# AST1032.net
KiCad netlist of a schematic drawn in EAGLE
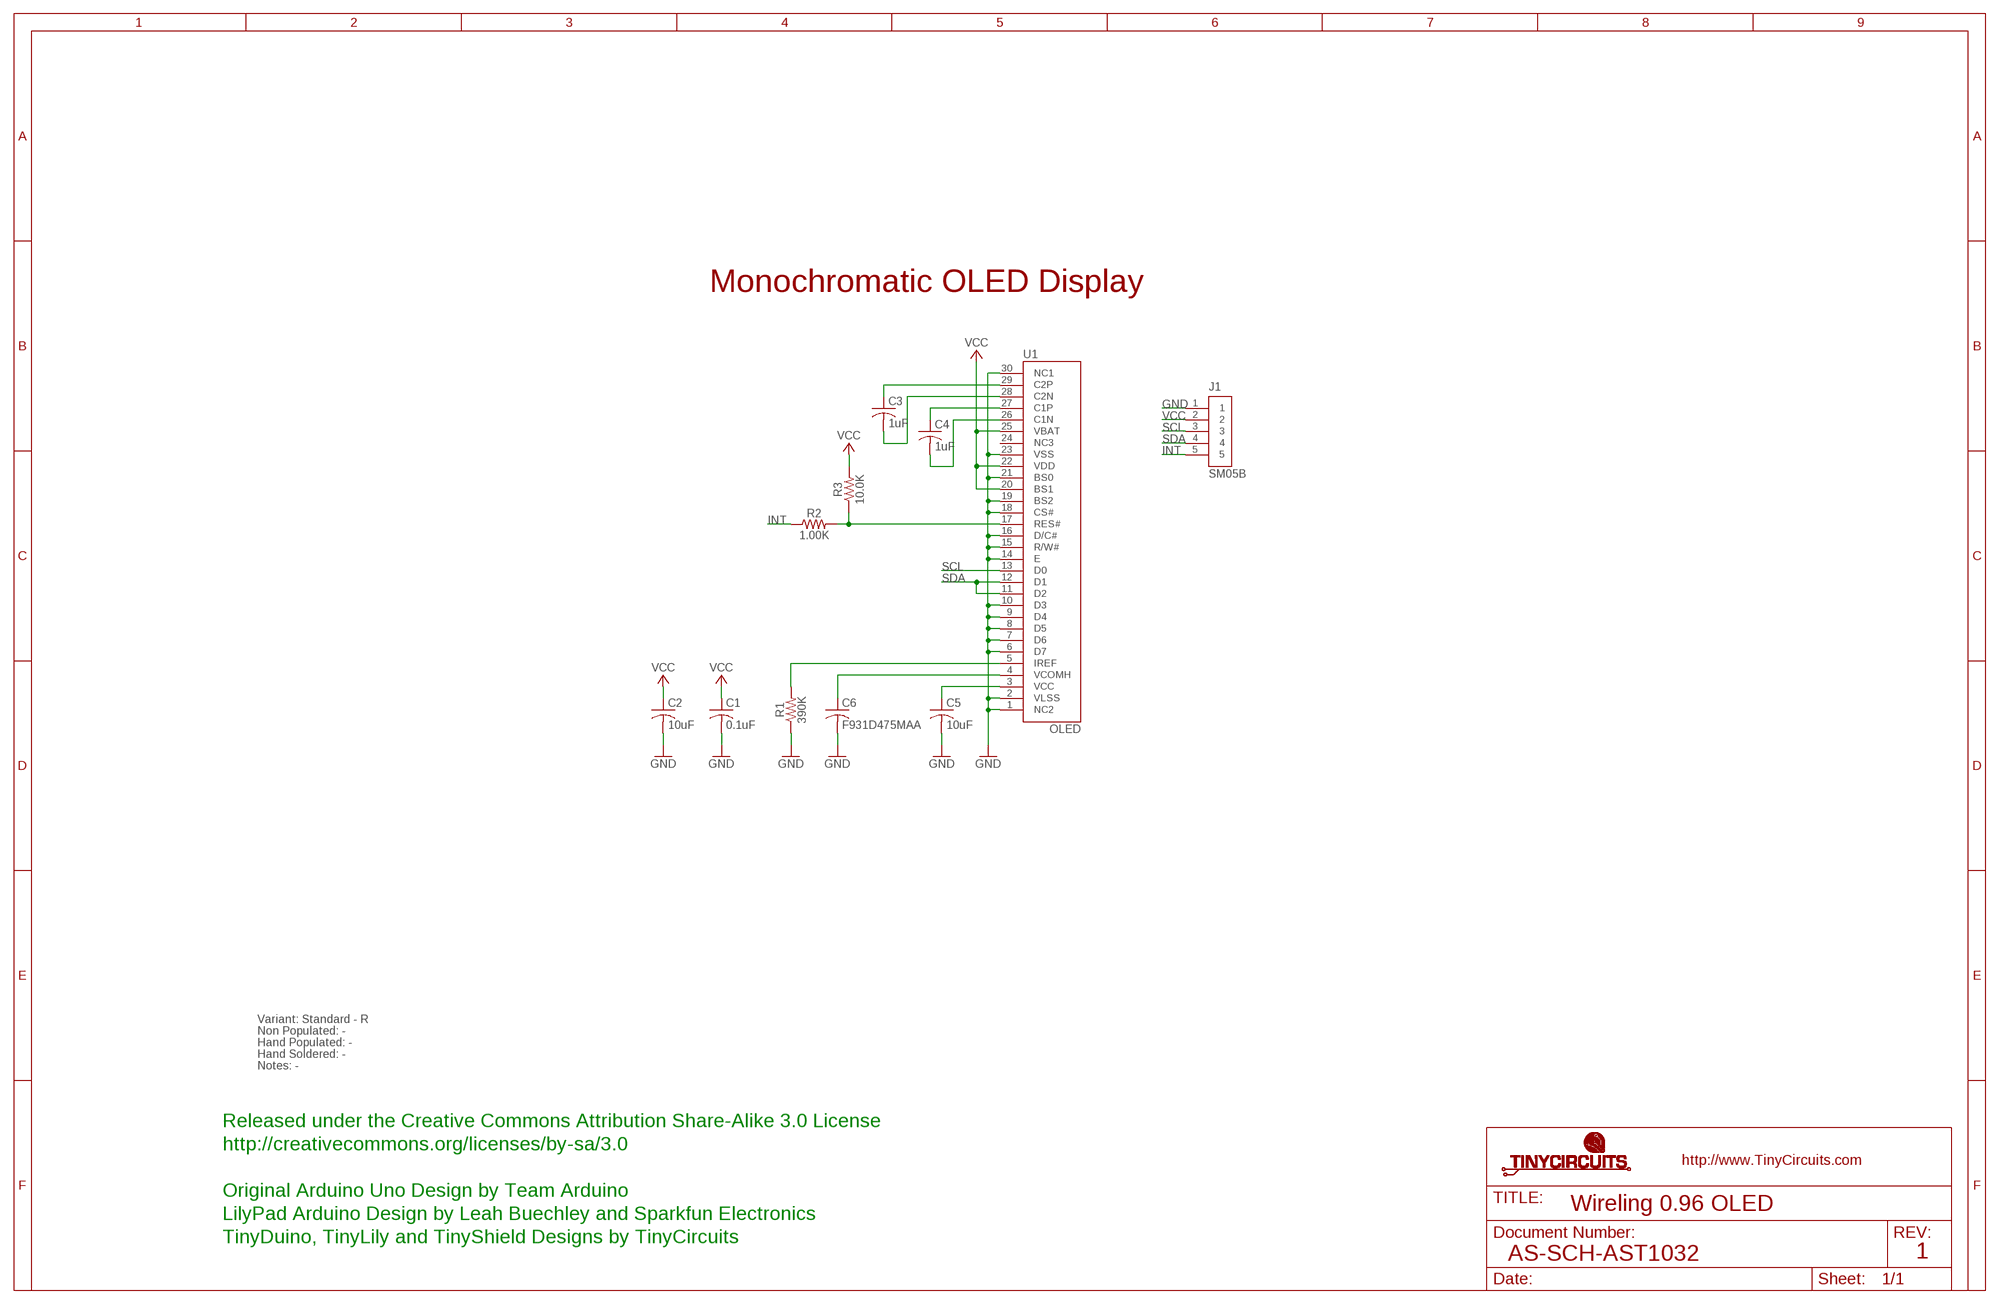
[diagram p0: schematic, sheet 1]

(export (version "E")
  (design (tool "Eeschema 10.0.6"))
  (components
    (comp (ref "C1")
      (value "0.1uF")
      (footprint "eagle-import:C0402")
      (fields (field (name "PARTNO") "AS-ITM-00008"))
      (libsource (lib "eagle-import") (part "AS-ITM-00008"))
    )
    (comp (ref "C2")
      (value "10uF")
      (footprint "eagle-import:C0603")
      (fields (field (name "PARTNO") "AS-ITM-00002"))
      (libsource (lib "eagle-import") (part "AS-ITM-00002"))
    )
    (comp (ref "C3")
      (value "1uF")
      (footprint "eagle-import:C0603")
      (fields (field (name "PARTNO") "AS-ITM-00347"))
      (libsource (lib "eagle-import") (part "AS-ITM-00347"))
    )
    (comp (ref "C4")
      (value "1uF")
      (footprint "eagle-import:C0603")
      (fields (field (name "PARTNO") "AS-ITM-00347"))
      (libsource (lib "eagle-import") (part "AS-ITM-00347"))
    )
    (comp (ref "C5")
      (value "10uF")
      (footprint "eagle-import:C0805")
      (fields (field (name "PARTNO") "AS-ITM-00045"))
      (libsource (lib "eagle-import") (part "AS-ITM-00045"))
    )
    (comp (ref "C6")
      (value "F931D475MAA")
      (footprint "eagle-import:1206_CAP_TANT")
      (fields (field (name "PARTNO") "AS-ITM-00232"))
      (libsource (lib "eagle-import") (part "AS-ITM-00232"))
    )
    (comp (ref "J1")
      (value "SM05B")
      (footprint "eagle-import:JST_SH_5X1")
      (fields (field (name "PARTNO") "AS-ITM-00340"))
      (libsource (lib "eagle-import") (part "AS-ITM-00340"))
    )
    (comp (ref "R1")
      (value "390K")
      (footprint "eagle-import:0402")
      (fields (field (name "PARTNO") "AS-ITM-00346"))
      (libsource (lib "eagle-import") (part "AS-ITM-00346"))
    )
    (comp (ref "R2")
      (value "1.00K")
      (footprint "eagle-import:0402")
      (fields (field (name "PARTNO") "AS-ITM-00003") (field (name "PARTNO_1") "AS-ITM-00003"))
      (libsource (lib "eagle-import") (part "AS-ITM-00003"))
    )
    (comp (ref "R3")
      (value "10.0K")
      (footprint "eagle-import:0402")
      (fields (field (name "PARTNO") "AS-ITM-00032"))
      (libsource (lib "eagle-import") (part "AS-ITM-00032"))
    )
    (comp (ref "U1")
      (value "OLED")
      (footprint "eagle-import:OLED_WHITE_30P")
      (fields (field (name "PARTNO") "AS-ITM-00341"))
      (libsource (lib "eagle-import") (part "AS-ITM-003411"))
    )
  )
  (nets
    (net (code "1") (name "/INT") (class "Default")
      (node (ref "J1") (pin "5") (pinfunction "5_5") (pintype "bidirectional"))
      (node (ref "R2") (pin "1") (pinfunction "1_1") (pintype "passive"))
    )
    (net (code "2") (name "/SCL") (class "Default")
      (node (ref "J1") (pin "3") (pinfunction "3_3") (pintype "bidirectional"))
      (node (ref "U1") (pin "13") (pinfunction "D0_13") (pintype "bidirectional"))
    )
    (net (code "3") (name "/SDA") (class "Default")
      (node (ref "J1") (pin "4") (pinfunction "4_4") (pintype "bidirectional"))
      (node (ref "U1") (pin "11") (pinfunction "D2_11") (pintype "bidirectional"))
      (node (ref "U1") (pin "12") (pinfunction "D1_12") (pintype "bidirectional"))
    )
    (net (code "4") (name "GND") (class "Default")
      (node (ref "C1") (pin "2") (pinfunction "2_2") (pintype "passive"))
      (node (ref "C2") (pin "2") (pinfunction "2_2") (pintype "passive"))
      (node (ref "C5") (pin "2") (pinfunction "2_2") (pintype "passive"))
      (node (ref "C6") (pin "2") (pinfunction "2_2") (pintype "passive"))
      (node (ref "J1") (pin "1") (pinfunction "1_1") (pintype "bidirectional"))
      (node (ref "R1") (pin "1") (pinfunction "1_1") (pintype "passive"))
      (node (ref "U1") (pin "1") (pinfunction "NC2_1") (pintype "bidirectional"))
      (node (ref "U1") (pin "10") (pinfunction "D3_10") (pintype "bidirectional"))
      (node (ref "U1") (pin "14") (pinfunction "E_14") (pintype "bidirectional"))
      (node (ref "U1") (pin "15") (pinfunction "R/W#_15") (pintype "bidirectional"))
      (node (ref "U1") (pin "16") (pinfunction "D/C#_16") (pintype "bidirectional"))
      (node (ref "U1") (pin "18") (pinfunction "CS#_18") (pintype "bidirectional"))
      (node (ref "U1") (pin "19") (pinfunction "BS2_19") (pintype "bidirectional"))
      (node (ref "U1") (pin "2") (pinfunction "VLSS_2") (pintype "bidirectional"))
      (node (ref "U1") (pin "21") (pinfunction "BS0_21") (pintype "bidirectional"))
      (node (ref "U1") (pin "23") (pinfunction "VSS_23") (pintype "bidirectional"))
      (node (ref "U1") (pin "30") (pinfunction "NC1_30") (pintype "bidirectional"))
      (node (ref "U1") (pin "6") (pinfunction "D7_6") (pintype "bidirectional"))
      (node (ref "U1") (pin "7") (pinfunction "D6_7") (pintype "bidirectional"))
      (node (ref "U1") (pin "8") (pinfunction "D5_8") (pintype "bidirectional"))
      (node (ref "U1") (pin "9") (pinfunction "D4_9") (pintype "bidirectional"))
    )
    (net (code "5") (name "Net-(U1-C1N)") (class "Default")
      (node (ref "C4") (pin "2") (pinfunction "2_2") (pintype "passive"))
      (node (ref "U1") (pin "26") (pinfunction "C1N_26") (pintype "bidirectional"))
    )
    (net (code "6") (name "Net-(U1-C1P)") (class "Default")
      (node (ref "C4") (pin "1") (pinfunction "1_1") (pintype "passive"))
      (node (ref "U1") (pin "27") (pinfunction "C1P_27") (pintype "bidirectional"))
    )
    (net (code "7") (name "Net-(U1-C2N)") (class "Default")
      (node (ref "C3") (pin "2") (pinfunction "2_2") (pintype "passive"))
      (node (ref "U1") (pin "28") (pinfunction "C2N_28") (pintype "bidirectional"))
    )
    (net (code "8") (name "Net-(U1-C2P)") (class "Default")
      (node (ref "C3") (pin "1") (pinfunction "1_1") (pintype "passive"))
      (node (ref "U1") (pin "29") (pinfunction "C2P_29") (pintype "bidirectional"))
    )
    (net (code "9") (name "Net-(U1-IREF)") (class "Default")
      (node (ref "R1") (pin "2") (pinfunction "2_2") (pintype "passive"))
      (node (ref "U1") (pin "5") (pinfunction "IREF_5") (pintype "bidirectional"))
    )
    (net (code "10") (name "Net-(U1-RES#)") (class "Default")
      (node (ref "R2") (pin "2") (pinfunction "2_2") (pintype "passive"))
      (node (ref "R3") (pin "1") (pinfunction "1_1") (pintype "passive"))
      (node (ref "U1") (pin "17") (pinfunction "RES#_17") (pintype "bidirectional"))
    )
    (net (code "11") (name "Net-(U1-VCC)") (class "Default")
      (node (ref "C5") (pin "1") (pinfunction "1_1") (pintype "passive"))
      (node (ref "U1") (pin "3") (pinfunction "VCC_3") (pintype "bidirectional"))
    )
    (net (code "12") (name "Net-(U1-VCOMH)") (class "Default")
      (node (ref "C6") (pin "1") (pinfunction "1_1") (pintype "passive"))
      (node (ref "U1") (pin "4") (pinfunction "VCOMH_4") (pintype "bidirectional"))
    )
    (net (code "13") (name "VCC") (class "Default")
      (node (ref "C1") (pin "1") (pinfunction "1_1") (pintype "passive"))
      (node (ref "C2") (pin "1") (pinfunction "1_1") (pintype "passive"))
      (node (ref "J1") (pin "2") (pinfunction "2_2") (pintype "bidirectional"))
      (node (ref "R3") (pin "2") (pinfunction "2_2") (pintype "passive"))
      (node (ref "U1") (pin "20") (pinfunction "BS1_20") (pintype "bidirectional"))
      (node (ref "U1") (pin "22") (pinfunction "VDD_22") (pintype "bidirectional"))
      (node (ref "U1") (pin "25") (pinfunction "VBAT_25") (pintype "bidirectional"))
    )
    (net (code "14") (name "unconnected-(U1-NC3-Pad24)") (class "Default")
      (node (ref "U1") (pin "24") (pinfunction "NC3_24") (pintype "bidirectional"))
    )
  )
)
